# pqc-rev1.net
KiCad netlist of a schematic drawn in EAGLE
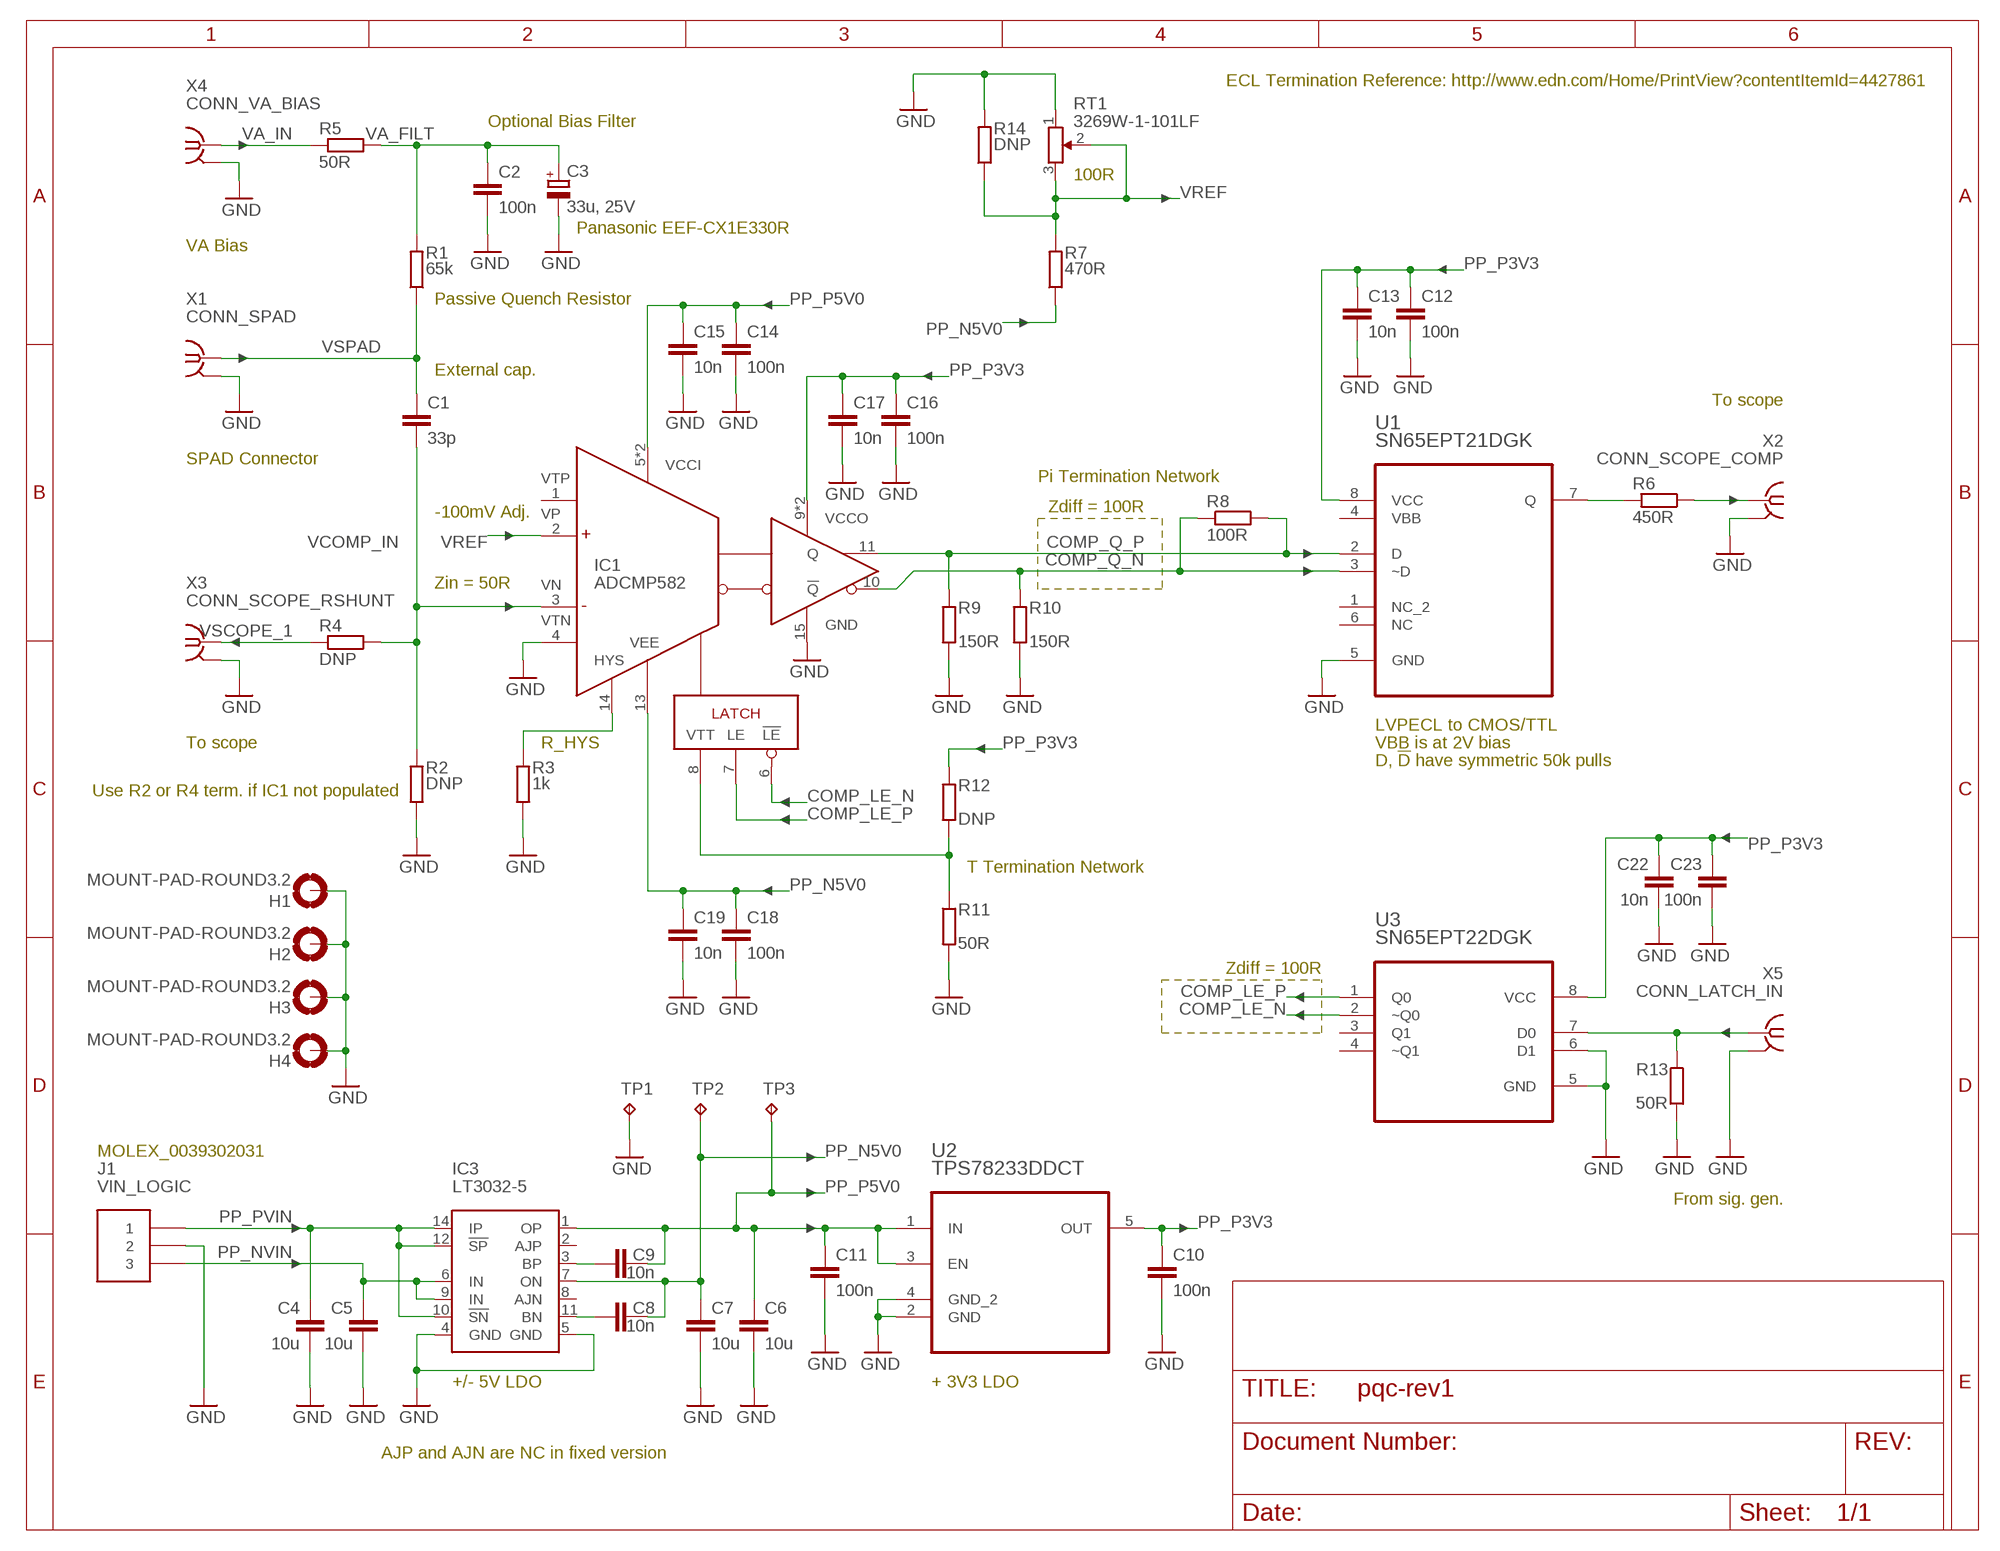
[diagram p0: schematic, sheet 1]

(export (version "E")
  (design (tool "Eeschema 10.0.6"))
  (components
    (comp (ref "C1")
      (value "33p")
      (footprint "eagle-import:C0805")
      (libsource (lib "eagle-import") (part "C-EUC0805"))
    )
    (comp (ref "C2")
      (value "100n")
      (footprint "eagle-import:C0805")
      (libsource (lib "eagle-import") (part "C-EUC0805"))
    )
    (comp (ref "C3")
      (value "33u, 25V")
      (footprint "eagle-import:CT7343")
      (libsource (lib "eagle-import") (part "CPOL-EUCT7343"))
    )
    (comp (ref "C4")
      (value "10u")
      (footprint "eagle-import:C1206")
      (libsource (lib "eagle-import") (part "C-EUC1206"))
    )
    (comp (ref "C5")
      (value "10u")
      (footprint "eagle-import:C1206")
      (libsource (lib "eagle-import") (part "C-EUC1206"))
    )
    (comp (ref "C6")
      (value "10u")
      (footprint "eagle-import:C1206")
      (libsource (lib "eagle-import") (part "C-EUC1206"))
    )
    (comp (ref "C7")
      (value "10u")
      (footprint "eagle-import:C1206")
      (libsource (lib "eagle-import") (part "C-EUC1206"))
    )
    (comp (ref "C8")
      (value "10n")
      (footprint "eagle-import:C0603")
      (libsource (lib "eagle-import") (part "C-EUC0603"))
    )
    (comp (ref "C9")
      (value "10n")
      (footprint "eagle-import:C0603")
      (libsource (lib "eagle-import") (part "C-EUC0603"))
    )
    (comp (ref "C10")
      (value "100n")
      (footprint "eagle-import:C0603")
      (libsource (lib "eagle-import") (part "C-EUC0603"))
    )
    (comp (ref "C11")
      (value "100n")
      (footprint "eagle-import:C0603")
      (libsource (lib "eagle-import") (part "C-EUC0603"))
    )
    (comp (ref "C12")
      (value "100n")
      (footprint "eagle-import:C0603")
      (libsource (lib "eagle-import") (part "C-EUC0603"))
    )
    (comp (ref "C13")
      (value "10n")
      (footprint "eagle-import:C0603")
      (libsource (lib "eagle-import") (part "C-EUC0603"))
    )
    (comp (ref "C14")
      (value "100n")
      (footprint "eagle-import:C0603")
      (libsource (lib "eagle-import") (part "C-EUC0603"))
    )
    (comp (ref "C15")
      (value "10n")
      (footprint "eagle-import:C0603")
      (libsource (lib "eagle-import") (part "C-EUC0603"))
    )
    (comp (ref "C16")
      (value "100n")
      (footprint "eagle-import:C0603")
      (libsource (lib "eagle-import") (part "C-EUC0603"))
    )
    (comp (ref "C17")
      (value "10n")
      (footprint "eagle-import:C0603")
      (libsource (lib "eagle-import") (part "C-EUC0603"))
    )
    (comp (ref "C18")
      (value "100n")
      (footprint "eagle-import:C0603")
      (libsource (lib "eagle-import") (part "C-EUC0603"))
    )
    (comp (ref "C19")
      (value "10n")
      (footprint "eagle-import:C0603")
      (libsource (lib "eagle-import") (part "C-EUC0603"))
    )
    (comp (ref "C22")
      (value "10n")
      (footprint "eagle-import:C0603")
      (libsource (lib "eagle-import") (part "C-EUC0603"))
    )
    (comp (ref "C23")
      (value "100n")
      (footprint "eagle-import:C0603")
      (libsource (lib "eagle-import") (part "C-EUC0603"))
    )
    (comp (ref "H1")
      (value "MOUNT-PAD-ROUND3.2")
      (footprint "eagle-import:3,2-PAD")
      (libsource (lib "eagle-import") (part "MOUNT-PAD-ROUND3.2"))
    )
    (comp (ref "H2")
      (value "MOUNT-PAD-ROUND3.2")
      (footprint "eagle-import:3,2-PAD")
      (libsource (lib "eagle-import") (part "MOUNT-PAD-ROUND3.2"))
    )
    (comp (ref "H3")
      (value "MOUNT-PAD-ROUND3.2")
      (footprint "eagle-import:3,2-PAD")
      (libsource (lib "eagle-import") (part "MOUNT-PAD-ROUND3.2"))
    )
    (comp (ref "H4")
      (value "MOUNT-PAD-ROUND3.2")
      (footprint "eagle-import:3,2-PAD")
      (libsource (lib "eagle-import") (part "MOUNT-PAD-ROUND3.2"))
    )
    (comp (ref "IC1")
      (value "ADCMP582")
      (footprint "eagle-import:QFN50P300X300X80-16N")
      (libsource (lib "eagle-import") (part "ADCMP582"))
    )
    (comp (ref "IC3")
      (value "LT3032-5")
      (footprint "eagle-import:DFN14-4X3DE")
      (libsource (lib "eagle-import") (part "LT3032"))
    )
    (comp (ref "J1")
      (value "VIN_LOGIC")
      (footprint "eagle-import:CONN_MOLEX_3PIN_MINI-FIT_JR")
      (libsource (lib "eagle-import") (part "CONN_MOLEX_3PIN_MINI-FIT_JR"))
    )
    (comp (ref "R1")
      (value "65k")
      (footprint "eagle-import:R0805")
      (libsource (lib "eagle-import") (part "R-EU_R0805"))
    )
    (comp (ref "R2")
      (value "DNP")
      (footprint "eagle-import:R0603")
      (libsource (lib "eagle-import") (part "R-EU_R0603"))
    )
    (comp (ref "R3")
      (value "1k")
      (footprint "eagle-import:R0805")
      (libsource (lib "eagle-import") (part "R-EU_R0805"))
    )
    (comp (ref "R4")
      (value "DNP")
      (footprint "eagle-import:R0603")
      (libsource (lib "eagle-import") (part "R-EU_R0603"))
    )
    (comp (ref "R5")
      (value "50R")
      (footprint "eagle-import:R0805")
      (libsource (lib "eagle-import") (part "R-EU_R0805"))
    )
    (comp (ref "R6")
      (value "450R")
      (footprint "eagle-import:R0805")
      (libsource (lib "eagle-import") (part "R-EU_R0805"))
    )
    (comp (ref "R7")
      (value "470R")
      (footprint "eagle-import:R0805")
      (libsource (lib "eagle-import") (part "R-EU_R0805"))
    )
    (comp (ref "R8")
      (value "100R")
      (footprint "eagle-import:R0603")
      (libsource (lib "eagle-import") (part "R-EU_R0603"))
    )
    (comp (ref "R9")
      (value "150R")
      (footprint "eagle-import:R0603")
      (libsource (lib "eagle-import") (part "R-EU_R0603"))
    )
    (comp (ref "R10")
      (value "150R")
      (footprint "eagle-import:R0603")
      (libsource (lib "eagle-import") (part "R-EU_R0603"))
    )
    (comp (ref "R11")
      (value "50R")
      (footprint "eagle-import:R0603")
      (libsource (lib "eagle-import") (part "R-EU_R0603"))
    )
    (comp (ref "R12")
      (value "DNP")
      (footprint "eagle-import:R0603")
      (libsource (lib "eagle-import") (part "R-EU_R0603"))
    )
    (comp (ref "R13")
      (value "50R")
      (footprint "eagle-import:R0603")
      (libsource (lib "eagle-import") (part "R-EU_R0603"))
    )
    (comp (ref "R14")
      (value "DNP")
      (footprint "eagle-import:R0805")
      (libsource (lib "eagle-import") (part "R-EU_R0805"))
    )
    (comp (ref "RT1")
      (value "3269W-1-101LF")
      (footprint "eagle-import:3269W")
      (libsource (lib "eagle-import") (part "BOURNS_3269WX"))
    )
    (comp (ref "TP1")
      (value "TPTP20R")
      (footprint "eagle-import:TP20R")
      (libsource (lib "eagle-import") (part "TPTP20R"))
    )
    (comp (ref "TP2")
      (value "TPTP20R")
      (footprint "eagle-import:TP20R")
      (libsource (lib "eagle-import") (part "TPTP20R"))
    )
    (comp (ref "TP3")
      (value "TPTP20R")
      (footprint "eagle-import:TP20R")
      (libsource (lib "eagle-import") (part "TPTP20R"))
    )
    (comp (ref "U1")
      (value "SN65EPT21DGK")
      (footprint "eagle-import:SOP65P490X110-8N")
      (libsource (lib "eagle-import") (part "SN65EPT21DGK"))
    )
    (comp (ref "U2")
      (value "TPS78233DDCT")
      (footprint "eagle-import:SOT95P280X110-5N")
      (libsource (lib "eagle-import") (part "TPS78233DDCT"))
    )
    (comp (ref "U3")
      (value "SN65EPT22DGK")
      (footprint "eagle-import:SOP65P490X110-8N")
      (libsource (lib "eagle-import") (part "SN65EPT22DGK"))
    )
    (comp (ref "X1")
      (value "CONN_SPAD")
      (footprint "eagle-import:J502-ND-142-0711-871_876")
      (fields (field (name "MF") "JOHNSON COMPONENTS") (field (name "MPN") "142-0711-871"))
      (libsource (lib "eagle-import") (part "SMA-142-0711-871/876"))
    )
    (comp (ref "X2")
      (value "CONN_SCOPE_COMP")
      (footprint "eagle-import:J502-ND-142-0711-871_876")
      (fields (field (name "MF") "JOHNSON COMPONENTS") (field (name "MPN") "142-0711-871"))
      (libsource (lib "eagle-import") (part "SMA-142-0711-871/876"))
    )
    (comp (ref "X3")
      (value "CONN_SCOPE_RSHUNT")
      (footprint "eagle-import:J502-ND-142-0711-871_876")
      (fields (field (name "MF") "JOHNSON COMPONENTS") (field (name "MPN") "142-0711-871"))
      (libsource (lib "eagle-import") (part "SMA-142-0711-871/876"))
    )
    (comp (ref "X4")
      (value "CONN_VA_BIAS")
      (footprint "eagle-import:J502-ND-142-0711-871_876")
      (fields (field (name "MF") "JOHNSON COMPONENTS") (field (name "MPN") "142-0711-871"))
      (libsource (lib "eagle-import") (part "SMA-142-0711-871/876"))
    )
    (comp (ref "X5")
      (value "CONN_LATCH_IN")
      (footprint "eagle-import:J502-ND-142-0711-871_876")
      (fields
        (field (name "MF") "JOHNSON COMPONENTS")
        (field (name "MPN") "142-0711-871")
        (field (name "MF_1") "JOHNSON COMPONENTS")
        (field (name "MPN_1") "142-0711-871")
        (field (name "OC_FARNELL") "unknown")
        (field (name "OC_NEWARK") "01C1639")
      )
      (libsource (lib "eagle-import") (part "SMA-142-0711-871/876"))
    )
  )
  (nets
    (net (code "1") (name "/COMP_LE_N") (class "Default")
      (node (ref "IC1") (pin "6") (pinfunction "~{LE}_6") (pintype "bidirectional"))
      (node (ref "U3") (pin "2") (pinfunction "~{Q0}_2") (pintype "output"))
    )
    (net (code "2") (name "/COMP_LE_P") (class "Default")
      (node (ref "IC1") (pin "7") (pinfunction "LE_7") (pintype "bidirectional"))
      (node (ref "U3") (pin "1") (pinfunction "Q0_1") (pintype "output"))
    )
    (net (code "3") (name "/COMP_Q_N") (class "Default")
      (node (ref "IC1") (pin "10") (pinfunction "~{Q}_10") (pintype "bidirectional"))
      (node (ref "R10") (pin "1") (pinfunction "1_1") (pintype "passive"))
      (node (ref "R8") (pin "1") (pinfunction "1_1") (pintype "passive"))
      (node (ref "U1") (pin "3") (pinfunction "~{D}_3") (pintype "input"))
    )
    (net (code "4") (name "/COMP_Q_P") (class "Default")
      (node (ref "IC1") (pin "11") (pinfunction "Q_11") (pintype "bidirectional"))
      (node (ref "R8") (pin "2") (pinfunction "2_2") (pintype "passive"))
      (node (ref "R9") (pin "1") (pinfunction "1_1") (pintype "passive"))
      (node (ref "U1") (pin "2") (pinfunction "D_2") (pintype "input"))
    )
    (net (code "5") (name "/PP_N5V0") (class "Default")
      (node (ref "C18") (pin "1") (pinfunction "1_1") (pintype "passive"))
      (node (ref "C19") (pin "1") (pinfunction "1_1") (pintype "passive"))
      (node (ref "C7") (pin "1") (pinfunction "1_1") (pintype "passive"))
      (node (ref "C8") (pin "2") (pinfunction "2_2") (pintype "passive"))
      (node (ref "IC1") (pin "13") (pinfunction "VEE_13") (pintype "bidirectional"))
      (node (ref "IC3") (pin "7") (pinfunction "ON_7") (pintype "power_in"))
      (node (ref "R7") (pin "1") (pinfunction "1_1") (pintype "passive"))
      (node (ref "TP2") (pin "TP") (pinfunction "TP_TP") (pintype "input"))
    )
    (net (code "6") (name "/PP_NVIN") (class "Default")
      (node (ref "C5") (pin "1") (pinfunction "1_1") (pintype "passive"))
      (node (ref "IC3") (pin "6") (pinfunction "IN_6") (pintype "power_in"))
      (node (ref "IC3") (pin "9") (pinfunction "IN_9") (pintype "power_in"))
      (node (ref "J1") (pin "3") (pinfunction "3_3") (pintype "bidirectional"))
    )
    (net (code "7") (name "/PP_P3V3") (class "Default")
      (node (ref "C10") (pin "1") (pinfunction "1_1") (pintype "passive"))
      (node (ref "C12") (pin "1") (pinfunction "1_1") (pintype "passive"))
      (node (ref "C13") (pin "1") (pinfunction "1_1") (pintype "passive"))
      (node (ref "C16") (pin "1") (pinfunction "1_1") (pintype "passive"))
      (node (ref "C17") (pin "1") (pinfunction "1_1") (pintype "passive"))
      (node (ref "C22") (pin "1") (pinfunction "1_1") (pintype "passive"))
      (node (ref "C23") (pin "1") (pinfunction "1_1") (pintype "passive"))
      (node (ref "IC1") (pin "12") (pinfunction "VCCO_12") (pintype "bidirectional"))
      (node (ref "IC1") (pin "9") (pinfunction "VCCO_9") (pintype "bidirectional"))
      (node (ref "R12") (pin "1") (pinfunction "1_1") (pintype "passive"))
      (node (ref "U1") (pin "8") (pinfunction "VCC_8") (pintype "power_in"))
      (node (ref "U2") (pin "5") (pinfunction "OUT_5") (pintype "output"))
      (node (ref "U3") (pin "8") (pinfunction "VCC_8") (pintype "power_in"))
    )
    (net (code "8") (name "/PP_P5V0") (class "Default")
      (node (ref "C11") (pin "1") (pinfunction "1_1") (pintype "passive"))
      (node (ref "C14") (pin "1") (pinfunction "1_1") (pintype "passive"))
      (node (ref "C15") (pin "1") (pinfunction "1_1") (pintype "passive"))
      (node (ref "C6") (pin "1") (pinfunction "1_1") (pintype "passive"))
      (node (ref "C9") (pin "2") (pinfunction "2_2") (pintype "passive"))
      (node (ref "IC1") (pin "16") (pinfunction "VCCI_16") (pintype "bidirectional"))
      (node (ref "IC1") (pin "5") (pinfunction "VCCI_5") (pintype "bidirectional"))
      (node (ref "IC3") (pin "1") (pinfunction "OP_1") (pintype "power_in"))
      (node (ref "TP3") (pin "TP") (pinfunction "TP_TP") (pintype "input"))
      (node (ref "U2") (pin "1") (pinfunction "IN_1") (pintype "input"))
      (node (ref "U2") (pin "3") (pinfunction "EN_3") (pintype "input"))
    )
    (net (code "9") (name "/PP_PVIN") (class "Default")
      (node (ref "C4") (pin "1") (pinfunction "1_1") (pintype "passive"))
      (node (ref "IC3") (pin "10") (pinfunction "~{SN}_10") (pintype "bidirectional"))
      (node (ref "IC3") (pin "12") (pinfunction "~{SP}_12") (pintype "bidirectional"))
      (node (ref "IC3") (pin "14") (pinfunction "IP_14") (pintype "power_in"))
      (node (ref "J1") (pin "1") (pinfunction "1_1") (pintype "bidirectional"))
    )
    (net (code "10") (name "/VA_FILT") (class "Default")
      (node (ref "C2") (pin "1") (pinfunction "1_1") (pintype "passive"))
      (node (ref "C3") (pin "+") (pinfunction "+_+") (pintype "passive"))
      (node (ref "R1") (pin "2") (pinfunction "2_2") (pintype "passive"))
      (node (ref "R5") (pin "1") (pinfunction "1_1") (pintype "passive"))
    )
    (net (code "11") (name "/VA_IN") (class "Default")
      (node (ref "R5") (pin "2") (pinfunction "2_2") (pintype "passive"))
      (node (ref "X4") (pin "1") (pinfunction "1_1") (pintype "passive"))
    )
    (net (code "12") (name "/VBB") (class "Default")
      (node (ref "U1") (pin "4") (pinfunction "VBB_4") (pintype "power_in"))
    )
    (net (code "13") (name "/VCOMP_IN") (class "Default")
      (node (ref "C1") (pin "2") (pinfunction "2_2") (pintype "passive"))
      (node (ref "IC1") (pin "3") (pinfunction "VN_3") (pintype "bidirectional"))
      (node (ref "R2") (pin "2") (pinfunction "2_2") (pintype "passive"))
      (node (ref "R4") (pin "1") (pinfunction "1_1") (pintype "passive"))
    )
    (net (code "14") (name "/VREF") (class "Default")
      (node (ref "IC1") (pin "2") (pinfunction "VP_2") (pintype "bidirectional"))
      (node (ref "R14") (pin "1") (pinfunction "1_1") (pintype "passive"))
      (node (ref "R7") (pin "2") (pinfunction "2_2") (pintype "passive"))
      (node (ref "RT1") (pin "2") (pinfunction "2_2") (pintype "bidirectional"))
      (node (ref "RT1") (pin "3") (pinfunction "3_3") (pintype "bidirectional"))
    )
    (net (code "15") (name "/VSCOPE_1") (class "Default")
      (node (ref "R4") (pin "2") (pinfunction "2_2") (pintype "passive"))
      (node (ref "X3") (pin "1") (pinfunction "1_1") (pintype "passive"))
    )
    (net (code "16") (name "/VSPAD") (class "Default")
      (node (ref "C1") (pin "1") (pinfunction "1_1") (pintype "passive"))
      (node (ref "R1") (pin "1") (pinfunction "1_1") (pintype "passive"))
      (node (ref "X1") (pin "1") (pinfunction "1_1") (pintype "passive"))
    )
    (net (code "17") (name "GND") (class "Default")
      (node (ref "C10") (pin "2") (pinfunction "2_2") (pintype "passive"))
      (node (ref "C11") (pin "2") (pinfunction "2_2") (pintype "passive"))
      (node (ref "C12") (pin "2") (pinfunction "2_2") (pintype "passive"))
      (node (ref "C13") (pin "2") (pinfunction "2_2") (pintype "passive"))
      (node (ref "C14") (pin "2") (pinfunction "2_2") (pintype "passive"))
      (node (ref "C15") (pin "2") (pinfunction "2_2") (pintype "passive"))
      (node (ref "C16") (pin "2") (pinfunction "2_2") (pintype "passive"))
      (node (ref "C17") (pin "2") (pinfunction "2_2") (pintype "passive"))
      (node (ref "C18") (pin "2") (pinfunction "2_2") (pintype "passive"))
      (node (ref "C19") (pin "2") (pinfunction "2_2") (pintype "passive"))
      (node (ref "C2") (pin "2") (pinfunction "2_2") (pintype "passive"))
      (node (ref "C22") (pin "2") (pinfunction "2_2") (pintype "passive"))
      (node (ref "C23") (pin "2") (pinfunction "2_2") (pintype "passive"))
      (node (ref "C3") (pin "-") (pinfunction "-_-") (pintype "passive"))
      (node (ref "C4") (pin "2") (pinfunction "2_2") (pintype "passive"))
      (node (ref "C5") (pin "2") (pinfunction "2_2") (pintype "passive"))
      (node (ref "C6") (pin "2") (pinfunction "2_2") (pintype "passive"))
      (node (ref "C7") (pin "2") (pinfunction "2_2") (pintype "passive"))
      (node (ref "H1") (pin "B3,2") (pinfunction "MOUNT_B3,2") (pintype "passive"))
      (node (ref "H2") (pin "B3,2") (pinfunction "MOUNT_B3,2") (pintype "passive"))
      (node (ref "H3") (pin "B3,2") (pinfunction "MOUNT_B3,2") (pintype "passive"))
      (node (ref "H4") (pin "B3,2") (pinfunction "MOUNT_B3,2") (pintype "passive"))
      (node (ref "IC1") (pin "15") (pinfunction "GND_15") (pintype "bidirectional"))
      (node (ref "IC1") (pin "4") (pinfunction "VTN_4") (pintype "bidirectional"))
      (node (ref "IC3") (pin "4") (pinfunction "GND_4") (pintype "power_in"))
      (node (ref "IC3") (pin "5") (pinfunction "GND_5") (pintype "power_in"))
      (node (ref "J1") (pin "2") (pinfunction "2_2") (pintype "bidirectional"))
      (node (ref "R10") (pin "2") (pinfunction "2_2") (pintype "passive"))
      (node (ref "R11") (pin "2") (pinfunction "2_2") (pintype "passive"))
      (node (ref "R13") (pin "2") (pinfunction "2_2") (pintype "passive"))
      (node (ref "R14") (pin "2") (pinfunction "2_2") (pintype "passive"))
      (node (ref "R2") (pin "1") (pinfunction "1_1") (pintype "passive"))
      (node (ref "R3") (pin "1") (pinfunction "1_1") (pintype "passive"))
      (node (ref "R9") (pin "2") (pinfunction "2_2") (pintype "passive"))
      (node (ref "RT1") (pin "1") (pinfunction "1_1") (pintype "bidirectional"))
      (node (ref "TP1") (pin "TP") (pinfunction "TP_TP") (pintype "input"))
      (node (ref "U1") (pin "5") (pinfunction "GND_5") (pintype "passive"))
      (node (ref "U2") (pin "2") (pinfunction "GND_2") (pintype "passive"))
      (node (ref "U2") (pin "4") (pinfunction "GND_2_4") (pintype "passive"))
      (node (ref "U3") (pin "5") (pinfunction "GND_5") (pintype "passive"))
      (node (ref "U3") (pin "6") (pinfunction "D1_6") (pintype "input"))
      (node (ref "X1") (pin "G@1") (pinfunction "GND_G@1") (pintype "power_in"))
      (node (ref "X2") (pin "G@1") (pinfunction "GND_G@1") (pintype "power_in"))
      (node (ref "X3") (pin "G@1") (pinfunction "GND_G@1") (pintype "power_in"))
      (node (ref "X4") (pin "G@1") (pinfunction "GND_G@1") (pintype "power_in"))
      (node (ref "X5") (pin "G@1") (pinfunction "GND_G@1") (pintype "power_in"))
    )
    (net (code "18") (name "Net-(IC1-HYS)") (class "Default")
      (node (ref "IC1") (pin "14") (pinfunction "HYS_14") (pintype "bidirectional"))
      (node (ref "R3") (pin "2") (pinfunction "2_2") (pintype "passive"))
    )
    (net (code "19") (name "Net-(IC1-VTT)") (class "Default")
      (node (ref "IC1") (pin "8") (pinfunction "VTT_8") (pintype "bidirectional"))
      (node (ref "R11") (pin "1") (pinfunction "1_1") (pintype "passive"))
      (node (ref "R12") (pin "2") (pinfunction "2_2") (pintype "passive"))
    )
    (net (code "20") (name "Net-(IC3-BN)") (class "Default")
      (node (ref "C8") (pin "1") (pinfunction "1_1") (pintype "passive"))
      (node (ref "IC3") (pin "11") (pinfunction "BN_11") (pintype "bidirectional"))
    )
    (net (code "21") (name "Net-(IC3-BP)") (class "Default")
      (node (ref "C9") (pin "1") (pinfunction "1_1") (pintype "passive"))
      (node (ref "IC3") (pin "3") (pinfunction "BP_3") (pintype "bidirectional"))
    )
    (net (code "22") (name "Net-(R6-Pad1)") (class "Default")
      (node (ref "R6") (pin "1") (pinfunction "1_1") (pintype "passive"))
      (node (ref "X2") (pin "1") (pinfunction "1_1") (pintype "passive"))
    )
    (net (code "23") (name "Net-(U1-Q)") (class "Default")
      (node (ref "R6") (pin "2") (pinfunction "2_2") (pintype "passive"))
      (node (ref "U1") (pin "7") (pinfunction "Q_7") (pintype "output"))
    )
    (net (code "24") (name "Net-(U3-D0)") (class "Default")
      (node (ref "R13") (pin "1") (pinfunction "1_1") (pintype "passive"))
      (node (ref "U3") (pin "7") (pinfunction "D0_7") (pintype "input"))
      (node (ref "X5") (pin "1") (pinfunction "1_1") (pintype "passive"))
    )
    (net (code "25") (name "unconnected-(IC1-VTP-Pad1)") (class "Default")
      (node (ref "IC1") (pin "1") (pinfunction "VTP_1") (pintype "bidirectional"))
    )
    (net (code "26") (name "unconnected-(IC3-AJN-Pad8)") (class "Default")
      (node (ref "IC3") (pin "8") (pinfunction "AJN_8") (pintype "bidirectional"))
    )
    (net (code "27") (name "unconnected-(IC3-AJP-Pad2)") (class "Default")
      (node (ref "IC3") (pin "2") (pinfunction "AJP_2") (pintype "bidirectional"))
    )
    (net (code "28") (name "unconnected-(U1-NC-Pad6)") (class "Default")
      (node (ref "U1") (pin "6") (pinfunction "NC_6") (pintype "no_connect"))
    )
    (net (code "29") (name "unconnected-(U1-NC_2-Pad1)") (class "Default")
      (node (ref "U1") (pin "1") (pinfunction "NC_2_1") (pintype "no_connect"))
    )
    (net (code "30") (name "unconnected-(U3-Q1-Pad3)") (class "Default")
      (node (ref "U3") (pin "3") (pinfunction "Q1_3") (pintype "output"))
    )
    (net (code "31") (name "unconnected-(U3-~{Q1}-Pad4)") (class "Default")
      (node (ref "U3") (pin "4") (pinfunction "~{Q1}_4") (pintype "output"))
    )
  )
)
